# Entradas.net
KiCad netlist of a schematic drawn in Altium Designer
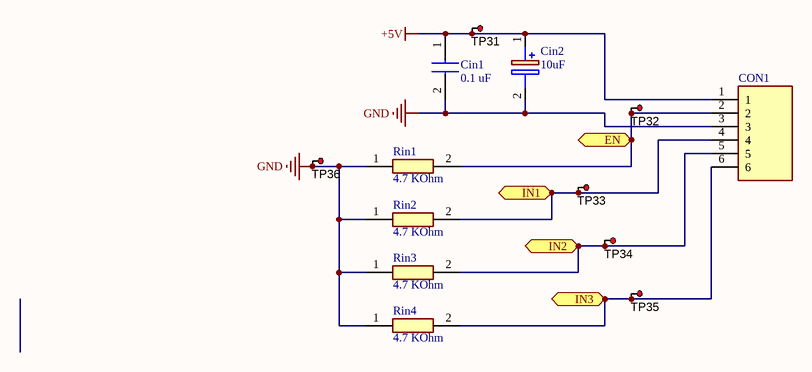
[diagram p0: Entradas.SchDoc]

(export (version "E")
  (design (tool "Eeschema 10.0.6"))
  (components
    (comp (ref "Cin1")
      (value "0.1 uF")
      (footprint "SamacSys:CAPC2012X94N")
      (description "Multilayer Ceramic Capacitors MLCC - SMD/SMT 16V .1uF X7R 0805 10%")
      (fields
        (field (name "MANUFACTURER_PART_NUMBER") "0805YC104KAT2A")
        (field (name "MOUSER PART NUMBER") "581-0805YC104K")
      )
      (libsource (lib "*") (part "0805YC104KAT2A"))
    )
    (comp (ref "Cin2")
      (value "10uF")
      (footprint "jasiel:CAPPM3216X180N - duplicate")
      (description "Cap Tant Solid 10uF 20V A CASE 20% (3.2 X 1.6 X 1.6mm) SMD 3216-18 3 Ohm 125C T/R")
      (fields
        (field (name "MANUFACTURER_PART_NUMBER") "T494A106M020AT")
        (field (name "MANUFACTURER") "KEMET")
      )
      (libsource (lib "sch jasiel") (part "T494A106M020AT"))
    )
    (comp (ref "CON1")
      (value "2350513-6")
      (footprint "SamacSys:23505136")
      (description "Connector")
      (fields (field (name "MANUFACTURER") "TE Connectivity"))
      (libsource (lib "sch jasiel") (part "2350513-6"))
    )
    (comp (ref "Rin1")
      (value "4.7 KOhm")
      (footprint "jasiel:RESC1608X55N - duplicate")
      (description "ESR03EZPJ472")
      (fields (field (name "MANUFACTURER") "Rohm") (field (name "TOLERANCE") "5%"))
      (libsource (lib "sch jasiel") (part "ESR03EZPJ472"))
    )
    (comp (ref "Rin2")
      (value "4.7 KOhm")
      (footprint "jasiel:RESC1608X55N - duplicate")
      (description "ESR03EZPJ472")
      (fields (field (name "MANUFACTURER") "Rohm") (field (name "TOLERANCE") "5%"))
      (libsource (lib "sch jasiel") (part "ESR03EZPJ472"))
    )
    (comp (ref "Rin3")
      (value "4.7 KOhm")
      (footprint "jasiel:RESC1608X55N - duplicate")
      (description "ESR03EZPJ472")
      (fields (field (name "MANUFACTURER") "Rohm") (field (name "TOLERANCE") "5%"))
      (libsource (lib "sch jasiel") (part "ESR03EZPJ472"))
    )
    (comp (ref "Rin4")
      (value "4.7 KOhm")
      (footprint "jasiel:RESC1608X55N - duplicate")
      (description "ESR03EZPJ472")
      (fields (field (name "MANUFACTURER") "Rohm") (field (name "TOLERANCE") "5%"))
      (libsource (lib "sch jasiel") (part "ESR03EZPJ472"))
    )
    (comp (ref "TP31")
      (value "5010")
      (footprint "Keystone5010")
      (description "Test Point, Multipurpose, Red, TH")
      (fields (field (name "MANUFACTURER") "Keystone") (field (name "PUBLISHER") "Texas Instruments"))
      (libsource (lib "sch jasiel") (part "5010"))
    )
    (comp (ref "TP32")
      (value "5010")
      (footprint "Keystone5010")
      (description "Test Point, Multipurpose, Red, TH")
      (fields (field (name "MANUFACTURER") "Keystone") (field (name "PUBLISHER") "Texas Instruments"))
      (libsource (lib "sch jasiel") (part "5010"))
    )
    (comp (ref "TP33")
      (value "5010")
      (footprint "Keystone5010")
      (description "Test Point, Multipurpose, Red, TH")
      (fields (field (name "MANUFACTURER") "Keystone") (field (name "PUBLISHER") "Texas Instruments"))
      (libsource (lib "sch jasiel") (part "5010"))
    )
    (comp (ref "TP34")
      (value "5010")
      (footprint "Keystone5010")
      (description "Test Point, Multipurpose, Red, TH")
      (fields (field (name "MANUFACTURER") "Keystone") (field (name "PUBLISHER") "Texas Instruments"))
      (libsource (lib "sch jasiel") (part "5010"))
    )
    (comp (ref "TP35")
      (value "5010")
      (footprint "Keystone5010")
      (description "Test Point, Multipurpose, Red, TH")
      (fields (field (name "MANUFACTURER") "Keystone") (field (name "PUBLISHER") "Texas Instruments"))
      (libsource (lib "sch jasiel") (part "5010"))
    )
    (comp (ref "TP36")
      (value "5010")
      (footprint "Keystone5010")
      (description "Test Point, Multipurpose, Red, TH")
      (fields (field (name "MANUFACTURER") "Keystone") (field (name "PUBLISHER") "Texas Instruments"))
      (libsource (lib "sch jasiel") (part "5010"))
    )
  )
  (nets
    (net (code "1") (name "+5V") (class "Default")
      (node (ref "CON1") (pin "1") (pinfunction "1_1") (pintype "passive"))
      (node (ref "Cin1") (pin "1") (pinfunction "1_1") (pintype "passive"))
      (node (ref "Cin2") (pin "1") (pinfunction "+_1") (pintype "passive"))
      (node (ref "TP31") (pin "1") (pinfunction "1_1") (pintype "passive"))
    )
    (net (code "2") (name "/EN") (class "Default")
      (node (ref "CON1") (pin "2") (pinfunction "2_2") (pintype "passive"))
      (node (ref "Rin1") (pin "2") (pinfunction "2_2") (pintype "passive"))
      (node (ref "TP32") (pin "1") (pinfunction "1_1") (pintype "passive"))
    )
    (net (code "3") (name "/IN1") (class "Default")
      (node (ref "CON1") (pin "4") (pinfunction "4_4") (pintype "passive"))
      (node (ref "Rin2") (pin "2") (pinfunction "2_2") (pintype "passive"))
      (node (ref "TP33") (pin "1") (pinfunction "1_1") (pintype "passive"))
    )
    (net (code "4") (name "/IN2") (class "Default")
      (node (ref "CON1") (pin "5") (pinfunction "5_5") (pintype "passive"))
      (node (ref "Rin3") (pin "2") (pinfunction "2_2") (pintype "passive"))
      (node (ref "TP34") (pin "1") (pinfunction "1_1") (pintype "passive"))
    )
    (net (code "5") (name "/IN3") (class "Default")
      (node (ref "CON1") (pin "6") (pinfunction "6_6") (pintype "passive"))
      (node (ref "Rin4") (pin "2") (pinfunction "2_2") (pintype "passive"))
      (node (ref "TP35") (pin "1") (pinfunction "1_1") (pintype "passive"))
    )
    (net (code "6") (name "GND") (class "Default")
      (node (ref "CON1") (pin "3") (pinfunction "3_3") (pintype "passive"))
      (node (ref "Cin1") (pin "2") (pinfunction "2_2") (pintype "passive"))
      (node (ref "Cin2") (pin "2") (pinfunction "-_2") (pintype "passive"))
      (node (ref "Rin1") (pin "1") (pinfunction "1_1") (pintype "passive"))
      (node (ref "Rin2") (pin "1") (pinfunction "1_1") (pintype "passive"))
      (node (ref "Rin3") (pin "1") (pinfunction "1_1") (pintype "passive"))
      (node (ref "Rin4") (pin "1") (pinfunction "1_1") (pintype "passive"))
      (node (ref "TP36") (pin "1") (pinfunction "1_1") (pintype "passive"))
    )
  )
)
